# leit-proto-1.net
KiCad netlist of a schematic drawn in EAGLE
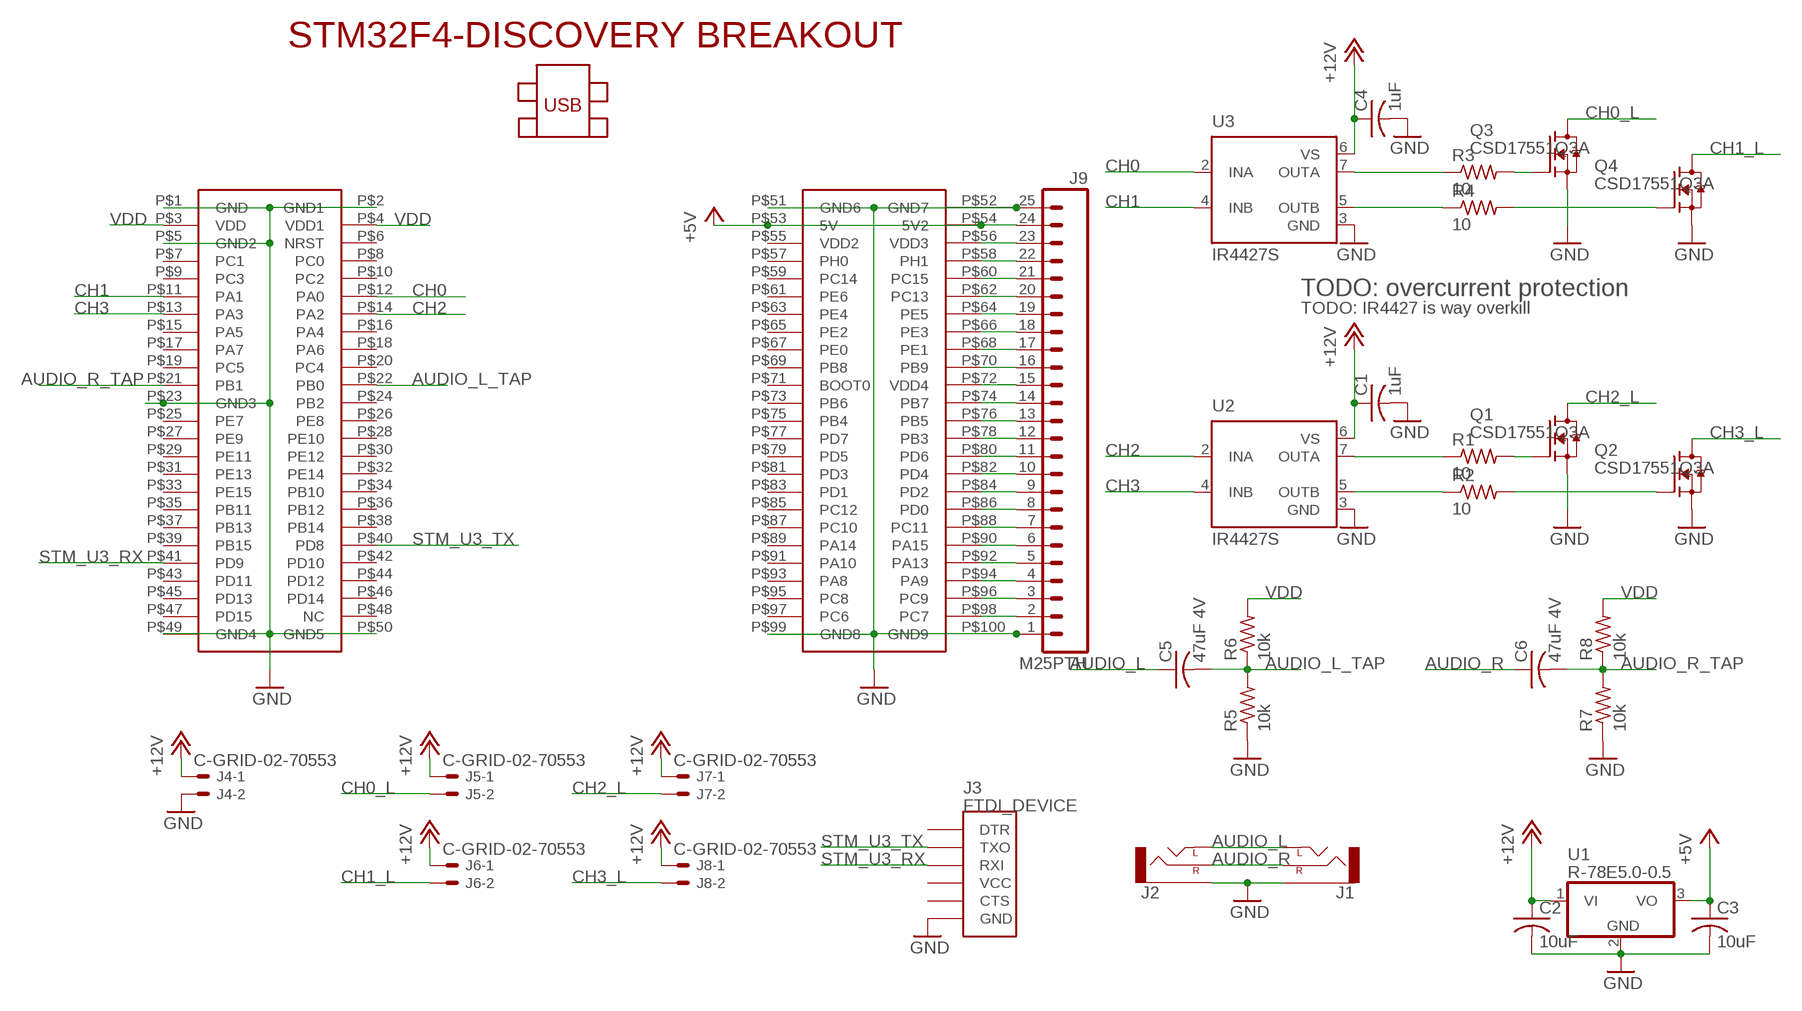
[diagram p0: schematic, sheet 1]

(export (version "E")
  (design (tool "Eeschema 10.0.6"))
  (components
    (comp (ref "C1")
      (value "1uF")
      (footprint "eagle-import:C0603")
      (libsource (lib "eagle-import") (part "C-USC0603"))
    )
    (comp (ref "C2")
      (value "10uF")
      (footprint "eagle-import:C0805")
      (libsource (lib "eagle-import") (part "C-USC0805"))
    )
    (comp (ref "C3")
      (value "10uF")
      (footprint "eagle-import:C0805")
      (libsource (lib "eagle-import") (part "C-USC0805"))
    )
    (comp (ref "C4")
      (value "1uF")
      (footprint "eagle-import:C0603")
      (libsource (lib "eagle-import") (part "C-USC0603"))
    )
    (comp (ref "C5")
      (value "47uF 4V")
      (footprint "eagle-import:C0805")
      (libsource (lib "eagle-import") (part "C-USC0805"))
    )
    (comp (ref "C6")
      (value "47uF 4V")
      (footprint "eagle-import:C0805")
      (libsource (lib "eagle-import") (part "C-USC0805"))
    )
    (comp (ref "J1")
      (value "AUDIO-JACKPTH")
      (footprint "eagle-import:AUDIO-JACK")
      (libsource (lib "eagle-import") (part "AUDIO-JACKPTH"))
    )
    (comp (ref "J2")
      (value "AUDIO-JACKPTH")
      (footprint "eagle-import:AUDIO-JACK")
      (libsource (lib "eagle-import") (part "AUDIO-JACKPTH"))
    )
    (comp (ref "J3")
      (value "FTDI_DEVICE")
      (footprint "eagle-import:FTDI_DEVICE_SIDE")
      (libsource (lib "eagle-import") (part "FTDI_DEVICE"))
    )
    (comp (ref "J4")
      (value "C-GRID-02-70553")
      (footprint "eagle-import:70553-02")
      (libsource (lib "eagle-import") (part "C-GRID-02-70553"))
    )
    (comp (ref "J5")
      (value "C-GRID-02-70553")
      (footprint "eagle-import:70553-02")
      (libsource (lib "eagle-import") (part "C-GRID-02-70553"))
    )
    (comp (ref "J6")
      (value "C-GRID-02-70553")
      (footprint "eagle-import:70553-02")
      (libsource (lib "eagle-import") (part "C-GRID-02-70553"))
    )
    (comp (ref "J7")
      (value "C-GRID-02-70553")
      (footprint "eagle-import:70553-02")
      (libsource (lib "eagle-import") (part "C-GRID-02-70553"))
    )
    (comp (ref "J8")
      (value "C-GRID-02-70553")
      (footprint "eagle-import:70553-02")
      (libsource (lib "eagle-import") (part "C-GRID-02-70553"))
    )
    (comp (ref "J9")
      (value "M25PTH")
      (footprint "eagle-import:1X25")
      (libsource (lib "eagle-import") (part "M25PTH"))
    )
    (comp (ref "MOD1")
      (value "STM32F4-DISCOVERY")
      (footprint "eagle-import:STM32F4-DISCOVERY")
      (libsource (lib "eagle-import") (part "STM32F4-DISCOVERY"))
    )
    (comp (ref "Q1")
      (value "CSD17551Q3A")
      (footprint "eagle-import:SON3.3")
      (libsource (lib "eagle-import") (part "CSD17551Q3A"))
    )
    (comp (ref "Q2")
      (value "CSD17551Q3A")
      (footprint "eagle-import:SON3.3")
      (libsource (lib "eagle-import") (part "CSD17551Q3A"))
    )
    (comp (ref "Q3")
      (value "CSD17551Q3A")
      (footprint "eagle-import:SON3.3")
      (libsource (lib "eagle-import") (part "CSD17551Q3A"))
    )
    (comp (ref "Q4")
      (value "CSD17551Q3A")
      (footprint "eagle-import:SON3.3")
      (libsource (lib "eagle-import") (part "CSD17551Q3A"))
    )
    (comp (ref "R1")
      (value "10")
      (footprint "eagle-import:R0603")
      (libsource (lib "eagle-import") (part "R-US_R0603"))
    )
    (comp (ref "R2")
      (value "10")
      (footprint "eagle-import:R0603")
      (libsource (lib "eagle-import") (part "R-US_R0603"))
    )
    (comp (ref "R3")
      (value "10")
      (footprint "eagle-import:R0603")
      (libsource (lib "eagle-import") (part "R-US_R0603"))
    )
    (comp (ref "R4")
      (value "10")
      (footprint "eagle-import:R0603")
      (libsource (lib "eagle-import") (part "R-US_R0603"))
    )
    (comp (ref "R5")
      (value "10k")
      (footprint "eagle-import:R0603")
      (libsource (lib "eagle-import") (part "R-US_R0603"))
    )
    (comp (ref "R6")
      (value "10k")
      (footprint "eagle-import:R0603")
      (libsource (lib "eagle-import") (part "R-US_R0603"))
    )
    (comp (ref "R7")
      (value "10k")
      (footprint "eagle-import:R0603")
      (libsource (lib "eagle-import") (part "R-US_R0603"))
    )
    (comp (ref "R8")
      (value "10k")
      (footprint "eagle-import:R0603")
      (libsource (lib "eagle-import") (part "R-US_R0603"))
    )
    (comp (ref "U1")
      (value "R-78E5.0-0.5")
      (footprint "eagle-import:TO220V")
      (libsource (lib "eagle-import") (part "78TV05"))
    )
    (comp (ref "U2")
      (value "IR4427S")
      (footprint "eagle-import:SO08")
      (fields (field (name "MF") "INTERNATIONAL RECTIFIER(IR)") (field (name "MPN") "IR4427STRPBF"))
      (libsource (lib "eagle-import") (part "IR4427S"))
    )
    (comp (ref "U3")
      (value "IR4427S")
      (footprint "eagle-import:SO08")
      (fields (field (name "MF") "INTERNATIONAL RECTIFIER(IR)") (field (name "MPN") "IR4427STRPBF"))
      (libsource (lib "eagle-import") (part "IR4427S"))
    )
  )
  (nets
    (net (code "1") (name "+5V") (class "Default")
      (node (ref "C3") (pin "1") (pinfunction "1_1") (pintype "passive"))
      (node (ref "J9") (pin "24") (pinfunction "24_24") (pintype "passive"))
      (node (ref "MOD1") (pin "P$53") (pinfunction "5V_P$53") (pintype "bidirectional"))
      (node (ref "MOD1") (pin "P$54") (pinfunction "5V2_P$54") (pintype "bidirectional"))
      (node (ref "U1") (pin "3") (pinfunction "VO_3") (pintype "passive"))
    )
    (net (code "2") (name "+12V") (class "Default")
      (node (ref "C1") (pin "1") (pinfunction "1_1") (pintype "passive"))
      (node (ref "C2") (pin "1") (pinfunction "1_1") (pintype "passive"))
      (node (ref "C4") (pin "1") (pinfunction "1_1") (pintype "passive"))
      (node (ref "J4") (pin "1") (pinfunction "S_1") (pintype "passive"))
      (node (ref "J5") (pin "1") (pinfunction "S_1") (pintype "passive"))
      (node (ref "J6") (pin "1") (pinfunction "S_1") (pintype "passive"))
      (node (ref "J7") (pin "1") (pinfunction "S_1") (pintype "passive"))
      (node (ref "J8") (pin "1") (pinfunction "S_1") (pintype "passive"))
      (node (ref "U1") (pin "1") (pinfunction "VI_1") (pintype "input"))
      (node (ref "U2") (pin "6") (pinfunction "VS_6") (pintype "power_in"))
      (node (ref "U3") (pin "6") (pinfunction "VS_6") (pintype "power_in"))
    )
    (net (code "3") (name "/AUDIO_L") (class "Default")
      (node (ref "C5") (pin "1") (pinfunction "1_1") (pintype "passive"))
      (node (ref "J1") (pin "TIP") (pinfunction "LEFT_TIP") (pintype "bidirectional"))
      (node (ref "J2") (pin "TIP") (pinfunction "LEFT_TIP") (pintype "bidirectional"))
    )
    (net (code "4") (name "/AUDIO_L_TAP") (class "Default")
      (node (ref "C5") (pin "2") (pinfunction "2_2") (pintype "passive"))
      (node (ref "MOD1") (pin "P$22") (pinfunction "PB0_P$22") (pintype "bidirectional"))
      (node (ref "R5") (pin "2") (pinfunction "2_2") (pintype "passive"))
      (node (ref "R6") (pin "1") (pinfunction "1_1") (pintype "passive"))
    )
    (net (code "5") (name "/AUDIO_R") (class "Default")
      (node (ref "C6") (pin "1") (pinfunction "1_1") (pintype "passive"))
      (node (ref "J1") (pin "RING") (pinfunction "RIGHT_RING") (pintype "bidirectional"))
      (node (ref "J2") (pin "RING") (pinfunction "RIGHT_RING") (pintype "bidirectional"))
    )
    (net (code "6") (name "/AUDIO_R_TAP") (class "Default")
      (node (ref "C6") (pin "2") (pinfunction "2_2") (pintype "passive"))
      (node (ref "MOD1") (pin "P$21") (pinfunction "PB1_P$21") (pintype "bidirectional"))
      (node (ref "R7") (pin "2") (pinfunction "2_2") (pintype "passive"))
      (node (ref "R8") (pin "1") (pinfunction "1_1") (pintype "passive"))
    )
    (net (code "7") (name "/CH0") (class "Default")
      (node (ref "MOD1") (pin "P$12") (pinfunction "PA0_P$12") (pintype "bidirectional"))
      (node (ref "U3") (pin "2") (pinfunction "INA_2") (pintype "input"))
    )
    (net (code "8") (name "/CH0_L") (class "Default")
      (node (ref "J5") (pin "2") (pinfunction "S_2") (pintype "passive"))
      (node (ref "Q3") (pin "5") (pinfunction "D_5") (pintype "passive"))
      (node (ref "Q3") (pin "6") (pinfunction "D_6") (pintype "passive"))
      (node (ref "Q3") (pin "7") (pinfunction "D_7") (pintype "passive"))
      (node (ref "Q3") (pin "8") (pinfunction "D_8") (pintype "passive"))
    )
    (net (code "9") (name "/CH1") (class "Default")
      (node (ref "MOD1") (pin "P$11") (pinfunction "PA1_P$11") (pintype "bidirectional"))
      (node (ref "U3") (pin "4") (pinfunction "INB_4") (pintype "input"))
    )
    (net (code "10") (name "/CH1_L") (class "Default")
      (node (ref "J6") (pin "2") (pinfunction "S_2") (pintype "passive"))
      (node (ref "Q4") (pin "5") (pinfunction "D_5") (pintype "passive"))
      (node (ref "Q4") (pin "6") (pinfunction "D_6") (pintype "passive"))
      (node (ref "Q4") (pin "7") (pinfunction "D_7") (pintype "passive"))
      (node (ref "Q4") (pin "8") (pinfunction "D_8") (pintype "passive"))
    )
    (net (code "11") (name "/CH2") (class "Default")
      (node (ref "MOD1") (pin "P$14") (pinfunction "PA2_P$14") (pintype "bidirectional"))
      (node (ref "U2") (pin "2") (pinfunction "INA_2") (pintype "input"))
    )
    (net (code "12") (name "/CH2_L") (class "Default")
      (node (ref "J7") (pin "2") (pinfunction "S_2") (pintype "passive"))
      (node (ref "Q1") (pin "5") (pinfunction "D_5") (pintype "passive"))
      (node (ref "Q1") (pin "6") (pinfunction "D_6") (pintype "passive"))
      (node (ref "Q1") (pin "7") (pinfunction "D_7") (pintype "passive"))
      (node (ref "Q1") (pin "8") (pinfunction "D_8") (pintype "passive"))
    )
    (net (code "13") (name "/CH3") (class "Default")
      (node (ref "MOD1") (pin "P$13") (pinfunction "PA3_P$13") (pintype "bidirectional"))
      (node (ref "U2") (pin "4") (pinfunction "INB_4") (pintype "input"))
    )
    (net (code "14") (name "/CH3_L") (class "Default")
      (node (ref "J8") (pin "2") (pinfunction "S_2") (pintype "passive"))
      (node (ref "Q2") (pin "5") (pinfunction "D_5") (pintype "passive"))
      (node (ref "Q2") (pin "6") (pinfunction "D_6") (pintype "passive"))
      (node (ref "Q2") (pin "7") (pinfunction "D_7") (pintype "passive"))
      (node (ref "Q2") (pin "8") (pinfunction "D_8") (pintype "passive"))
    )
    (net (code "15") (name "/STM_U3_RX") (class "Default")
      (node (ref "J3") (pin "P$3") (pinfunction "RXI_P$3") (pintype "bidirectional"))
      (node (ref "MOD1") (pin "P$41") (pinfunction "PD9_P$41") (pintype "bidirectional"))
    )
    (net (code "16") (name "/STM_U3_TX") (class "Default")
      (node (ref "J3") (pin "P$2") (pinfunction "TXO_P$2") (pintype "bidirectional"))
      (node (ref "MOD1") (pin "P$40") (pinfunction "PD8_P$40") (pintype "bidirectional"))
    )
    (net (code "17") (name "/VDD") (class "Default")
      (node (ref "MOD1") (pin "P$3") (pinfunction "VDD_P$3") (pintype "bidirectional"))
      (node (ref "MOD1") (pin "P$4") (pinfunction "VDD1_P$4") (pintype "bidirectional"))
      (node (ref "R6") (pin "2") (pinfunction "2_2") (pintype "passive"))
      (node (ref "R8") (pin "2") (pinfunction "2_2") (pintype "passive"))
    )
    (net (code "18") (name "GND") (class "Default")
      (node (ref "C1") (pin "2") (pinfunction "2_2") (pintype "passive"))
      (node (ref "C2") (pin "2") (pinfunction "2_2") (pintype "passive"))
      (node (ref "C3") (pin "2") (pinfunction "2_2") (pintype "passive"))
      (node (ref "C4") (pin "2") (pinfunction "2_2") (pintype "passive"))
      (node (ref "J1") (pin "SLEEVE") (pinfunction "SLEEVE_SLEEVE") (pintype "bidirectional"))
      (node (ref "J2") (pin "SLEEVE") (pinfunction "SLEEVE_SLEEVE") (pintype "bidirectional"))
      (node (ref "J3") (pin "P$6") (pinfunction "GND_P$6") (pintype "bidirectional"))
      (node (ref "J4") (pin "2") (pinfunction "S_2") (pintype "passive"))
      (node (ref "J9") (pin "1") (pinfunction "1_1") (pintype "passive"))
      (node (ref "J9") (pin "25") (pinfunction "25_25") (pintype "passive"))
      (node (ref "MOD1") (pin "P$1") (pinfunction "GND_P$1") (pintype "bidirectional"))
      (node (ref "MOD1") (pin "P$100") (pinfunction "GND9_P$100") (pintype "bidirectional"))
      (node (ref "MOD1") (pin "P$2") (pinfunction "GND1_P$2") (pintype "bidirectional"))
      (node (ref "MOD1") (pin "P$23") (pinfunction "GND3_P$23") (pintype "bidirectional"))
      (node (ref "MOD1") (pin "P$49") (pinfunction "GND4_P$49") (pintype "bidirectional"))
      (node (ref "MOD1") (pin "P$5") (pinfunction "GND2_P$5") (pintype "bidirectional"))
      (node (ref "MOD1") (pin "P$50") (pinfunction "GND5_P$50") (pintype "bidirectional"))
      (node (ref "MOD1") (pin "P$51") (pinfunction "GND6_P$51") (pintype "bidirectional"))
      (node (ref "MOD1") (pin "P$52") (pinfunction "GND7_P$52") (pintype "bidirectional"))
      (node (ref "MOD1") (pin "P$99") (pinfunction "GND8_P$99") (pintype "bidirectional"))
      (node (ref "Q1") (pin "1") (pinfunction "S_1") (pintype "passive"))
      (node (ref "Q1") (pin "2") (pinfunction "S_2") (pintype "passive"))
      (node (ref "Q1") (pin "3") (pinfunction "S_3") (pintype "passive"))
      (node (ref "Q2") (pin "1") (pinfunction "S_1") (pintype "passive"))
      (node (ref "Q2") (pin "2") (pinfunction "S_2") (pintype "passive"))
      (node (ref "Q2") (pin "3") (pinfunction "S_3") (pintype "passive"))
      (node (ref "Q3") (pin "1") (pinfunction "S_1") (pintype "passive"))
      (node (ref "Q3") (pin "2") (pinfunction "S_2") (pintype "passive"))
      (node (ref "Q3") (pin "3") (pinfunction "S_3") (pintype "passive"))
      (node (ref "Q4") (pin "1") (pinfunction "S_1") (pintype "passive"))
      (node (ref "Q4") (pin "2") (pinfunction "S_2") (pintype "passive"))
      (node (ref "Q4") (pin "3") (pinfunction "S_3") (pintype "passive"))
      (node (ref "R5") (pin "1") (pinfunction "1_1") (pintype "passive"))
      (node (ref "R7") (pin "1") (pinfunction "1_1") (pintype "passive"))
      (node (ref "U1") (pin "2") (pinfunction "GND_2") (pintype "passive"))
      (node (ref "U2") (pin "3") (pinfunction "GND_3") (pintype "power_in"))
      (node (ref "U3") (pin "3") (pinfunction "GND_3") (pintype "power_in"))
    )
    (net (code "19") (name "Net-(MOD1-PA9)") (class "Default")
      (node (ref "J9") (pin "4") (pinfunction "4_4") (pintype "passive"))
      (node (ref "MOD1") (pin "P$94") (pinfunction "PA9_P$94") (pintype "bidirectional"))
    )
    (net (code "20") (name "Net-(MOD1-PA13)") (class "Default")
      (node (ref "J9") (pin "5") (pinfunction "5_5") (pintype "passive"))
      (node (ref "MOD1") (pin "P$92") (pinfunction "PA13_P$92") (pintype "bidirectional"))
    )
    (net (code "21") (name "Net-(MOD1-PA15)") (class "Default")
      (node (ref "J9") (pin "6") (pinfunction "6_6") (pintype "passive"))
      (node (ref "MOD1") (pin "P$90") (pinfunction "PA15_P$90") (pintype "bidirectional"))
    )
    (net (code "22") (name "Net-(MOD1-PB3)") (class "Default")
      (node (ref "J9") (pin "12") (pinfunction "12_12") (pintype "passive"))
      (node (ref "MOD1") (pin "P$78") (pinfunction "PB3_P$78") (pintype "bidirectional"))
    )
    (net (code "23") (name "Net-(MOD1-PB5)") (class "Default")
      (node (ref "J9") (pin "13") (pinfunction "13_13") (pintype "passive"))
      (node (ref "MOD1") (pin "P$76") (pinfunction "PB5_P$76") (pintype "bidirectional"))
    )
    (net (code "24") (name "Net-(MOD1-PB7)") (class "Default")
      (node (ref "J9") (pin "14") (pinfunction "14_14") (pintype "passive"))
      (node (ref "MOD1") (pin "P$74") (pinfunction "PB7_P$74") (pintype "bidirectional"))
    )
    (net (code "25") (name "Net-(MOD1-PB9)") (class "Default")
      (node (ref "J9") (pin "16") (pinfunction "16_16") (pintype "passive"))
      (node (ref "MOD1") (pin "P$70") (pinfunction "PB9_P$70") (pintype "bidirectional"))
    )
    (net (code "26") (name "Net-(MOD1-PC7)") (class "Default")
      (node (ref "J9") (pin "2") (pinfunction "2_2") (pintype "passive"))
      (node (ref "MOD1") (pin "P$98") (pinfunction "PC7_P$98") (pintype "bidirectional"))
    )
    (net (code "27") (name "Net-(MOD1-PC9)") (class "Default")
      (node (ref "J9") (pin "3") (pinfunction "3_3") (pintype "passive"))
      (node (ref "MOD1") (pin "P$96") (pinfunction "PC9_P$96") (pintype "bidirectional"))
    )
    (net (code "28") (name "Net-(MOD1-PC11)") (class "Default")
      (node (ref "J9") (pin "7") (pinfunction "7_7") (pintype "passive"))
      (node (ref "MOD1") (pin "P$88") (pinfunction "PC11_P$88") (pintype "bidirectional"))
    )
    (net (code "29") (name "Net-(MOD1-PC13)") (class "Default")
      (node (ref "J9") (pin "20") (pinfunction "20_20") (pintype "passive"))
      (node (ref "MOD1") (pin "P$62") (pinfunction "PC13_P$62") (pintype "bidirectional"))
    )
    (net (code "30") (name "Net-(MOD1-PC15)") (class "Default")
      (node (ref "J9") (pin "21") (pinfunction "21_21") (pintype "passive"))
      (node (ref "MOD1") (pin "P$60") (pinfunction "PC15_P$60") (pintype "bidirectional"))
    )
    (net (code "31") (name "Net-(MOD1-PD0)") (class "Default")
      (node (ref "J9") (pin "8") (pinfunction "8_8") (pintype "passive"))
      (node (ref "MOD1") (pin "P$86") (pinfunction "PD0_P$86") (pintype "bidirectional"))
    )
    (net (code "32") (name "Net-(MOD1-PD2)") (class "Default")
      (node (ref "J9") (pin "9") (pinfunction "9_9") (pintype "passive"))
      (node (ref "MOD1") (pin "P$84") (pinfunction "PD2_P$84") (pintype "bidirectional"))
    )
    (net (code "33") (name "Net-(MOD1-PD4)") (class "Default")
      (node (ref "J9") (pin "10") (pinfunction "10_10") (pintype "passive"))
      (node (ref "MOD1") (pin "P$82") (pinfunction "PD4_P$82") (pintype "bidirectional"))
    )
    (net (code "34") (name "Net-(MOD1-PD6)") (class "Default")
      (node (ref "J9") (pin "11") (pinfunction "11_11") (pintype "passive"))
      (node (ref "MOD1") (pin "P$80") (pinfunction "PD6_P$80") (pintype "bidirectional"))
    )
    (net (code "35") (name "Net-(MOD1-PE1)") (class "Default")
      (node (ref "J9") (pin "17") (pinfunction "17_17") (pintype "passive"))
      (node (ref "MOD1") (pin "P$68") (pinfunction "PE1_P$68") (pintype "bidirectional"))
    )
    (net (code "36") (name "Net-(MOD1-PE3)") (class "Default")
      (node (ref "J9") (pin "18") (pinfunction "18_18") (pintype "passive"))
      (node (ref "MOD1") (pin "P$66") (pinfunction "PE3_P$66") (pintype "bidirectional"))
    )
    (net (code "37") (name "Net-(MOD1-PE5)") (class "Default")
      (node (ref "J9") (pin "19") (pinfunction "19_19") (pintype "passive"))
      (node (ref "MOD1") (pin "P$64") (pinfunction "PE5_P$64") (pintype "bidirectional"))
    )
    (net (code "38") (name "Net-(MOD1-PH1)") (class "Default")
      (node (ref "J9") (pin "22") (pinfunction "22_22") (pintype "passive"))
      (node (ref "MOD1") (pin "P$58") (pinfunction "PH1_P$58") (pintype "bidirectional"))
    )
    (net (code "39") (name "Net-(MOD1-VDD3)") (class "Default")
      (node (ref "J9") (pin "23") (pinfunction "23_23") (pintype "passive"))
      (node (ref "MOD1") (pin "P$56") (pinfunction "VDD3_P$56") (pintype "bidirectional"))
    )
    (net (code "40") (name "Net-(MOD1-VDD4)") (class "Default")
      (node (ref "J9") (pin "15") (pinfunction "15_15") (pintype "passive"))
      (node (ref "MOD1") (pin "P$72") (pinfunction "VDD4_P$72") (pintype "bidirectional"))
    )
    (net (code "41") (name "Net-(Q1-G)") (class "Default")
      (node (ref "Q1") (pin "4") (pinfunction "G_4") (pintype "passive"))
      (node (ref "R1") (pin "2") (pinfunction "2_2") (pintype "passive"))
    )
    (net (code "42") (name "Net-(Q2-G)") (class "Default")
      (node (ref "Q2") (pin "4") (pinfunction "G_4") (pintype "passive"))
      (node (ref "R2") (pin "2") (pinfunction "2_2") (pintype "passive"))
    )
    (net (code "43") (name "Net-(Q3-G)") (class "Default")
      (node (ref "Q3") (pin "4") (pinfunction "G_4") (pintype "passive"))
      (node (ref "R3") (pin "2") (pinfunction "2_2") (pintype "passive"))
    )
    (net (code "44") (name "Net-(Q4-G)") (class "Default")
      (node (ref "Q4") (pin "4") (pinfunction "G_4") (pintype "passive"))
      (node (ref "R4") (pin "2") (pinfunction "2_2") (pintype "passive"))
    )
    (net (code "45") (name "Net-(U2-OUTA)") (class "Default")
      (node (ref "R1") (pin "1") (pinfunction "1_1") (pintype "passive"))
      (node (ref "U2") (pin "7") (pinfunction "OUTA_7") (pintype "output"))
    )
    (net (code "46") (name "Net-(U2-OUTB)") (class "Default")
      (node (ref "R2") (pin "1") (pinfunction "1_1") (pintype "passive"))
      (node (ref "U2") (pin "5") (pinfunction "OUTB_5") (pintype "output"))
    )
    (net (code "47") (name "Net-(U3-OUTA)") (class "Default")
      (node (ref "R3") (pin "1") (pinfunction "1_1") (pintype "passive"))
      (node (ref "U3") (pin "7") (pinfunction "OUTA_7") (pintype "output"))
    )
    (net (code "48") (name "Net-(U3-OUTB)") (class "Default")
      (node (ref "R4") (pin "1") (pinfunction "1_1") (pintype "passive"))
      (node (ref "U3") (pin "5") (pinfunction "OUTB_5") (pintype "output"))
    )
    (net (code "49") (name "unconnected-(J3-CTS-PadP$5)") (class "Default")
      (node (ref "J3") (pin "P$5") (pinfunction "CTS_P$5") (pintype "bidirectional"))
    )
    (net (code "50") (name "unconnected-(J3-DTR-PadP$1)") (class "Default")
      (node (ref "J3") (pin "P$1") (pinfunction "DTR_P$1") (pintype "bidirectional"))
    )
    (net (code "51") (name "unconnected-(J3-VCC-PadP$4)") (class "Default")
      (node (ref "J3") (pin "P$4") (pinfunction "VCC_P$4") (pintype "bidirectional"))
    )
    (net (code "52") (name "unconnected-(MOD1-BOOT0-PadP$71)") (class "Default")
      (node (ref "MOD1") (pin "P$71") (pinfunction "BOOT0_P$71") (pintype "bidirectional"))
    )
    (net (code "53") (name "unconnected-(MOD1-NC-PadP$48)") (class "Default")
      (node (ref "MOD1") (pin "P$48") (pinfunction "NC_P$48") (pintype "bidirectional"))
    )
    (net (code "54") (name "unconnected-(MOD1-NRST-PadP$6)") (class "Default")
      (node (ref "MOD1") (pin "P$6") (pinfunction "NRST_P$6") (pintype "bidirectional"))
    )
    (net (code "55") (name "unconnected-(MOD1-PA4-PadP$16)") (class "Default")
      (node (ref "MOD1") (pin "P$16") (pinfunction "PA4_P$16") (pintype "bidirectional"))
    )
    (net (code "56") (name "unconnected-(MOD1-PA5-PadP$15)") (class "Default")
      (node (ref "MOD1") (pin "P$15") (pinfunction "PA5_P$15") (pintype "bidirectional"))
    )
    (net (code "57") (name "unconnected-(MOD1-PA6-PadP$18)") (class "Default")
      (node (ref "MOD1") (pin "P$18") (pinfunction "PA6_P$18") (pintype "bidirectional"))
    )
    (net (code "58") (name "unconnected-(MOD1-PA7-PadP$17)") (class "Default")
      (node (ref "MOD1") (pin "P$17") (pinfunction "PA7_P$17") (pintype "bidirectional"))
    )
    (net (code "59") (name "unconnected-(MOD1-PA8-PadP$93)") (class "Default")
      (node (ref "MOD1") (pin "P$93") (pinfunction "PA8_P$93") (pintype "bidirectional"))
    )
    (net (code "60") (name "unconnected-(MOD1-PA10-PadP$91)") (class "Default")
      (node (ref "MOD1") (pin "P$91") (pinfunction "PA10_P$91") (pintype "bidirectional"))
    )
    (net (code "61") (name "unconnected-(MOD1-PA14-PadP$89)") (class "Default")
      (node (ref "MOD1") (pin "P$89") (pinfunction "PA14_P$89") (pintype "bidirectional"))
    )
    (net (code "62") (name "unconnected-(MOD1-PB2-PadP$24)") (class "Default")
      (node (ref "MOD1") (pin "P$24") (pinfunction "PB2_P$24") (pintype "bidirectional"))
    )
    (net (code "63") (name "unconnected-(MOD1-PB4-PadP$75)") (class "Default")
      (node (ref "MOD1") (pin "P$75") (pinfunction "PB4_P$75") (pintype "bidirectional"))
    )
    (net (code "64") (name "unconnected-(MOD1-PB6-PadP$73)") (class "Default")
      (node (ref "MOD1") (pin "P$73") (pinfunction "PB6_P$73") (pintype "bidirectional"))
    )
    (net (code "65") (name "unconnected-(MOD1-PB8-PadP$69)") (class "Default")
      (node (ref "MOD1") (pin "P$69") (pinfunction "PB8_P$69") (pintype "bidirectional"))
    )
    (net (code "66") (name "unconnected-(MOD1-PB10-PadP$34)") (class "Default")
      (node (ref "MOD1") (pin "P$34") (pinfunction "PB10_P$34") (pintype "bidirectional"))
    )
    (net (code "67") (name "unconnected-(MOD1-PB11-PadP$35)") (class "Default")
      (node (ref "MOD1") (pin "P$35") (pinfunction "PB11_P$35") (pintype "bidirectional"))
    )
    (net (code "68") (name "unconnected-(MOD1-PB12-PadP$36)") (class "Default")
      (node (ref "MOD1") (pin "P$36") (pinfunction "PB12_P$36") (pintype "bidirectional"))
    )
    (net (code "69") (name "unconnected-(MOD1-PB13-PadP$37)") (class "Default")
      (node (ref "MOD1") (pin "P$37") (pinfunction "PB13_P$37") (pintype "bidirectional"))
    )
    (net (code "70") (name "unconnected-(MOD1-PB14-PadP$38)") (class "Default")
      (node (ref "MOD1") (pin "P$38") (pinfunction "PB14_P$38") (pintype "bidirectional"))
    )
    (net (code "71") (name "unconnected-(MOD1-PB15-PadP$39)") (class "Default")
      (node (ref "MOD1") (pin "P$39") (pinfunction "PB15_P$39") (pintype "bidirectional"))
    )
    (net (code "72") (name "unconnected-(MOD1-PC0-PadP$8)") (class "Default")
      (node (ref "MOD1") (pin "P$8") (pinfunction "PC0_P$8") (pintype "bidirectional"))
    )
    (net (code "73") (name "unconnected-(MOD1-PC1-PadP$7)") (class "Default")
      (node (ref "MOD1") (pin "P$7") (pinfunction "PC1_P$7") (pintype "bidirectional"))
    )
    (net (code "74") (name "unconnected-(MOD1-PC2-PadP$10)") (class "Default")
      (node (ref "MOD1") (pin "P$10") (pinfunction "PC2_P$10") (pintype "bidirectional"))
    )
    (net (code "75") (name "unconnected-(MOD1-PC3-PadP$9)") (class "Default")
      (node (ref "MOD1") (pin "P$9") (pinfunction "PC3_P$9") (pintype "bidirectional"))
    )
    (net (code "76") (name "unconnected-(MOD1-PC4-PadP$20)") (class "Default")
      (node (ref "MOD1") (pin "P$20") (pinfunction "PC4_P$20") (pintype "bidirectional"))
    )
    (net (code "77") (name "unconnected-(MOD1-PC5-PadP$19)") (class "Default")
      (node (ref "MOD1") (pin "P$19") (pinfunction "PC5_P$19") (pintype "bidirectional"))
    )
    (net (code "78") (name "unconnected-(MOD1-PC6-PadP$97)") (class "Default")
      (node (ref "MOD1") (pin "P$97") (pinfunction "PC6_P$97") (pintype "bidirectional"))
    )
    (net (code "79") (name "unconnected-(MOD1-PC8-PadP$95)") (class "Default")
      (node (ref "MOD1") (pin "P$95") (pinfunction "PC8_P$95") (pintype "bidirectional"))
    )
    (net (code "80") (name "unconnected-(MOD1-PC10-PadP$87)") (class "Default")
      (node (ref "MOD1") (pin "P$87") (pinfunction "PC10_P$87") (pintype "bidirectional"))
    )
    (net (code "81") (name "unconnected-(MOD1-PC12-PadP$85)") (class "Default")
      (node (ref "MOD1") (pin "P$85") (pinfunction "PC12_P$85") (pintype "bidirectional"))
    )
    (net (code "82") (name "unconnected-(MOD1-PC14-PadP$59)") (class "Default")
      (node (ref "MOD1") (pin "P$59") (pinfunction "PC14_P$59") (pintype "bidirectional"))
    )
    (net (code "83") (name "unconnected-(MOD1-PD1-PadP$83)") (class "Default")
      (node (ref "MOD1") (pin "P$83") (pinfunction "PD1_P$83") (pintype "bidirectional"))
    )
    (net (code "84") (name "unconnected-(MOD1-PD3-PadP$81)") (class "Default")
      (node (ref "MOD1") (pin "P$81") (pinfunction "PD3_P$81") (pintype "bidirectional"))
    )
    (net (code "85") (name "unconnected-(MOD1-PD5-PadP$79)") (class "Default")
      (node (ref "MOD1") (pin "P$79") (pinfunction "PD5_P$79") (pintype "bidirectional"))
    )
    (net (code "86") (name "unconnected-(MOD1-PD7-PadP$77)") (class "Default")
      (node (ref "MOD1") (pin "P$77") (pinfunction "PD7_P$77") (pintype "bidirectional"))
    )
    (net (code "87") (name "unconnected-(MOD1-PD10-PadP$42)") (class "Default")
      (node (ref "MOD1") (pin "P$42") (pinfunction "PD10_P$42") (pintype "bidirectional"))
    )
    (net (code "88") (name "unconnected-(MOD1-PD11-PadP$43)") (class "Default")
      (node (ref "MOD1") (pin "P$43") (pinfunction "PD11_P$43") (pintype "bidirectional"))
    )
    (net (code "89") (name "unconnected-(MOD1-PD12-PadP$44)") (class "Default")
      (node (ref "MOD1") (pin "P$44") (pinfunction "PD12_P$44") (pintype "bidirectional"))
    )
    (net (code "90") (name "unconnected-(MOD1-PD13-PadP$45)") (class "Default")
      (node (ref "MOD1") (pin "P$45") (pinfunction "PD13_P$45") (pintype "bidirectional"))
    )
    (net (code "91") (name "unconnected-(MOD1-PD14-PadP$46)") (class "Default")
      (node (ref "MOD1") (pin "P$46") (pinfunction "PD14_P$46") (pintype "bidirectional"))
    )
    (net (code "92") (name "unconnected-(MOD1-PD15-PadP$47)") (class "Default")
      (node (ref "MOD1") (pin "P$47") (pinfunction "PD15_P$47") (pintype "bidirectional"))
    )
    (net (code "93") (name "unconnected-(MOD1-PE0-PadP$67)") (class "Default")
      (node (ref "MOD1") (pin "P$67") (pinfunction "PE0_P$67") (pintype "bidirectional"))
    )
    (net (code "94") (name "unconnected-(MOD1-PE2-PadP$65)") (class "Default")
      (node (ref "MOD1") (pin "P$65") (pinfunction "PE2_P$65") (pintype "bidirectional"))
    )
    (net (code "95") (name "unconnected-(MOD1-PE4-PadP$63)") (class "Default")
      (node (ref "MOD1") (pin "P$63") (pinfunction "PE4_P$63") (pintype "bidirectional"))
    )
    (net (code "96") (name "unconnected-(MOD1-PE6-PadP$61)") (class "Default")
      (node (ref "MOD1") (pin "P$61") (pinfunction "PE6_P$61") (pintype "bidirectional"))
    )
    (net (code "97") (name "unconnected-(MOD1-PE7-PadP$25)") (class "Default")
      (node (ref "MOD1") (pin "P$25") (pinfunction "PE7_P$25") (pintype "bidirectional"))
    )
    (net (code "98") (name "unconnected-(MOD1-PE8-PadP$26)") (class "Default")
      (node (ref "MOD1") (pin "P$26") (pinfunction "PE8_P$26") (pintype "bidirectional"))
    )
    (net (code "99") (name "unconnected-(MOD1-PE9-PadP$27)") (class "Default")
      (node (ref "MOD1") (pin "P$27") (pinfunction "PE9_P$27") (pintype "bidirectional"))
    )
    (net (code "100") (name "unconnected-(MOD1-PE10-PadP$28)") (class "Default")
      (node (ref "MOD1") (pin "P$28") (pinfunction "PE10_P$28") (pintype "bidirectional"))
    )
    (net (code "101") (name "unconnected-(MOD1-PE11-PadP$29)") (class "Default")
      (node (ref "MOD1") (pin "P$29") (pinfunction "PE11_P$29") (pintype "bidirectional"))
    )
    (net (code "102") (name "unconnected-(MOD1-PE12-PadP$30)") (class "Default")
      (node (ref "MOD1") (pin "P$30") (pinfunction "PE12_P$30") (pintype "bidirectional"))
    )
    (net (code "103") (name "unconnected-(MOD1-PE13-PadP$31)") (class "Default")
      (node (ref "MOD1") (pin "P$31") (pinfunction "PE13_P$31") (pintype "bidirectional"))
    )
    (net (code "104") (name "unconnected-(MOD1-PE14-PadP$32)") (class "Default")
      (node (ref "MOD1") (pin "P$32") (pinfunction "PE14_P$32") (pintype "bidirectional"))
    )
    (net (code "105") (name "unconnected-(MOD1-PE15-PadP$33)") (class "Default")
      (node (ref "MOD1") (pin "P$33") (pinfunction "PE15_P$33") (pintype "bidirectional"))
    )
    (net (code "106") (name "unconnected-(MOD1-PH0-PadP$57)") (class "Default")
      (node (ref "MOD1") (pin "P$57") (pinfunction "PH0_P$57") (pintype "bidirectional"))
    )
    (net (code "107") (name "unconnected-(MOD1-VDD2-PadP$55)") (class "Default")
      (node (ref "MOD1") (pin "P$55") (pinfunction "VDD2_P$55") (pintype "bidirectional"))
    )
  )
)
